# Power_Distribution_-_Spare_1-4.net
KiCad netlist of a schematic drawn in Altium Designer
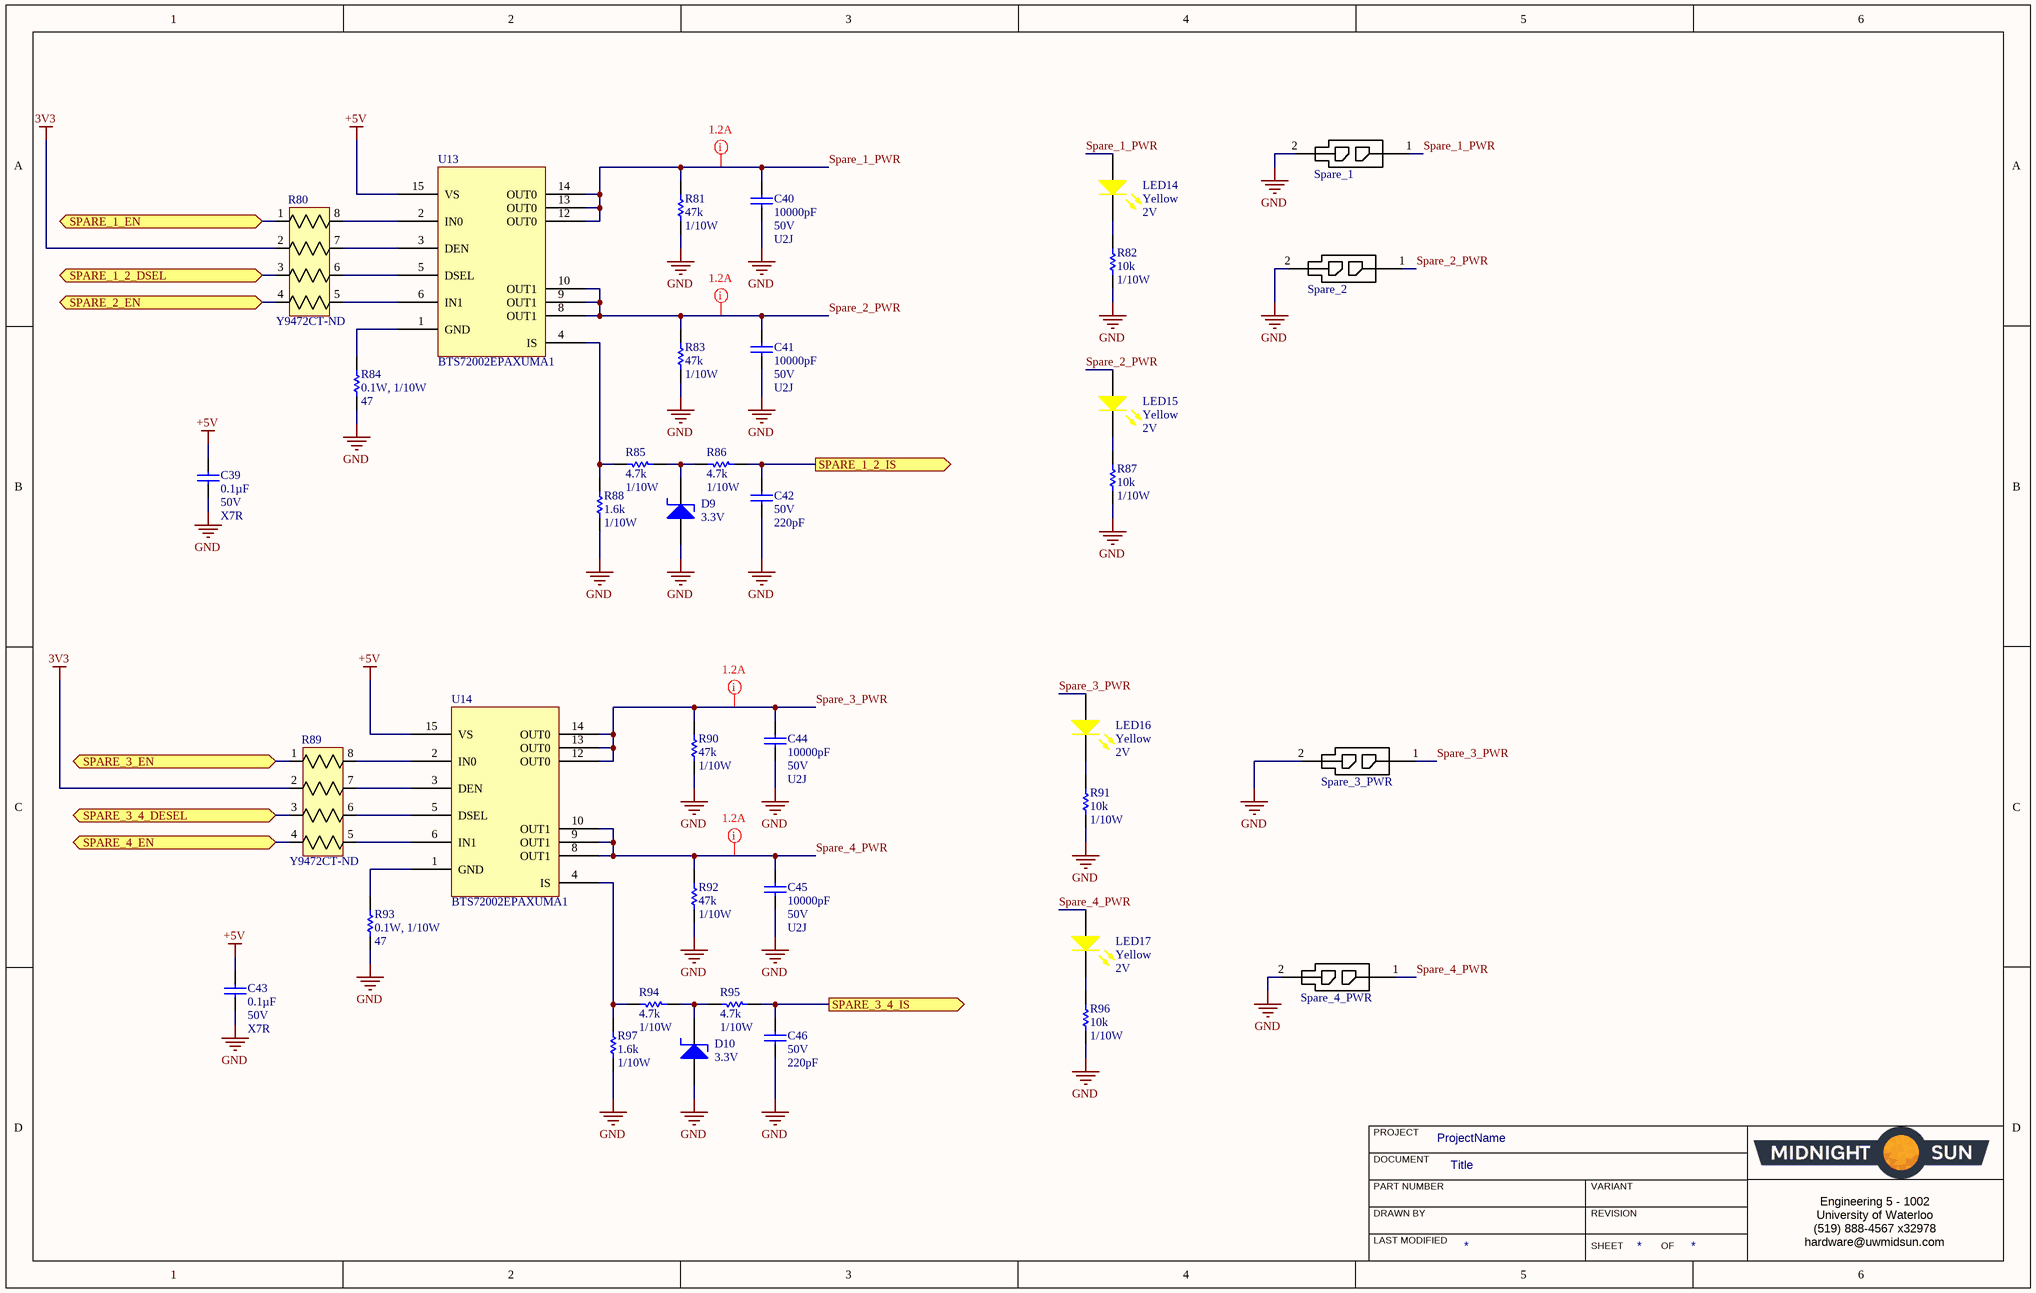
[diagram p0: Power Distribution - Spare 1-4.SchDoc]

(export (version "E")
  (design (tool "Eeschema 10.0.6"))
  (components
    (comp (ref "C39")
      (value "CAP CER 0.1UF 50V 10% X7R 0603")
      (footprint "CAP, 0603")
      (description "0.10µF ±10% 50V Ceramic Capacitor X7R 0603 (1608 Metric)")
      (fields
        (field (name "TOLERANCE") "±10%")
        (field (name "CAPACITANCE") "0.1µF")
        (field (name "VOLTAGE") "50V")
        (field (name "TEMPERATURE COEFFICIENT") "X7R")
      )
      (libsource (lib "Schematic Diagrams") (part "CAP CER 0.1UF 50V 10% X7R 0603"))
    )
    (comp (ref "C40")
      (value "CAP CER 10nF 50V 5% X7R 0603")
      (footprint "CAP, 0603")
      (description "10000pF ±5% 50V Ceramic Capacitor U2J 0603 (1608 Metric)")
      (fields
        (field (name "TOLERANCE") "±5%")
        (field (name "CAPACITANCE") "10000pF")
        (field (name "VOLTAGE") "50V")
        (field (name "TEMPERATURE COEFFICIENT") "U2J")
      )
      (libsource (lib "Schematic Diagrams") (part "CAP CER 10nF 50V 5% X7R 0603"))
    )
    (comp (ref "C41")
      (value "CAP CER 10nF 50V 5% X7R 0603")
      (footprint "CAP, 0603")
      (description "10000pF ±5% 50V Ceramic Capacitor U2J 0603 (1608 Metric)")
      (fields
        (field (name "TOLERANCE") "±5%")
        (field (name "CAPACITANCE") "10000pF")
        (field (name "VOLTAGE") "50V")
        (field (name "TEMPERATURE COEFFICIENT") "U2J")
      )
      (libsource (lib "Schematic Diagrams") (part "CAP CER 10nF 50V 5% X7R 0603"))
    )
    (comp (ref "C42")
      (value "CAP CER 220PF 50V C0G/NP0 0603")
      (footprint "CAP, 0603")
      (description "220pF ±5% 50V Ceramic Capacitor C0G, NP0 0603 (1608 Metric)")
      (fields
        (field (name "MANUFACTURER") "KEMET")
        (field (name "TOLERANCE") "5%")
        (field (name "VOLTAGE RATING") "50V")
        (field (name "CAPACITANCE") "220pF")
      )
      (libsource (lib "Schematic Diagrams") (part "CAP CER 220PF 50V C0G/NP0 0603"))
    )
    (comp (ref "C43")
      (value "CAP CER 0.1UF 50V 10% X7R 0603")
      (footprint "CAP, 0603")
      (description "0.10µF ±10% 50V Ceramic Capacitor X7R 0603 (1608 Metric)")
      (fields
        (field (name "TOLERANCE") "±10%")
        (field (name "CAPACITANCE") "0.1µF")
        (field (name "VOLTAGE") "50V")
        (field (name "TEMPERATURE COEFFICIENT") "X7R")
      )
      (libsource (lib "Schematic Diagrams") (part "CAP CER 0.1UF 50V 10% X7R 0603"))
    )
    (comp (ref "C44")
      (value "CAP CER 10nF 50V 5% X7R 0603")
      (footprint "CAP, 0603")
      (description "10000pF ±5% 50V Ceramic Capacitor U2J 0603 (1608 Metric)")
      (fields
        (field (name "TOLERANCE") "±5%")
        (field (name "CAPACITANCE") "10000pF")
        (field (name "VOLTAGE") "50V")
        (field (name "TEMPERATURE COEFFICIENT") "U2J")
      )
      (libsource (lib "Schematic Diagrams") (part "CAP CER 10nF 50V 5% X7R 0603"))
    )
    (comp (ref "C45")
      (value "CAP CER 10nF 50V 5% X7R 0603")
      (footprint "CAP, 0603")
      (description "10000pF ±5% 50V Ceramic Capacitor U2J 0603 (1608 Metric)")
      (fields
        (field (name "TOLERANCE") "±5%")
        (field (name "CAPACITANCE") "10000pF")
        (field (name "VOLTAGE") "50V")
        (field (name "TEMPERATURE COEFFICIENT") "U2J")
      )
      (libsource (lib "Schematic Diagrams") (part "CAP CER 10nF 50V 5% X7R 0603"))
    )
    (comp (ref "C46")
      (value "CAP CER 220PF 50V C0G/NP0 0603")
      (footprint "CAP, 0603")
      (description "220pF ±5% 50V Ceramic Capacitor C0G, NP0 0603 (1608 Metric)")
      (fields
        (field (name "MANUFACTURER") "KEMET")
        (field (name "TOLERANCE") "5%")
        (field (name "VOLTAGE RATING") "50V")
        (field (name "CAPACITANCE") "220pF")
      )
      (libsource (lib "Schematic Diagrams") (part "CAP CER 220PF 50V C0G/NP0 0603"))
    )
    (comp (ref "D9")
      (value "DIODE ZENER 3.3V 200MW SOD323")
      (footprint "sod-323")
      (description "Zener Diode 3.3V 200mW ±5% Surface Mount SOD-323")
      (fields (field (name "VOLTAGE") "3.3V"))
      (libsource (lib "Schematic Diagrams") (part "DIODE ZENER 3.3V 200MW SOD323"))
    )
    (comp (ref "D10")
      (value "DIODE ZENER 3.3V 200MW SOD323")
      (footprint "sod-323")
      (description "Zener Diode 3.3V 200mW ±5% Surface Mount SOD-323")
      (fields (field (name "VOLTAGE") "3.3V"))
      (libsource (lib "Schematic Diagrams") (part "DIODE ZENER 3.3V 200MW SOD323"))
    )
    (comp (ref "LED14")
      (value "LED YELLOW CLEAR 2.1V 0603")
      (footprint "LED_0603")
      (description "Yellow 590nm LED Indication - Discrete 2V 0603 (1608 Metric)")
      (fields
        (field (name "MANUFACTURER") "Wurth Electronics Inc.")
        (field (name "MANUFACTURER PART NUMBER") "150060YS75000")
        (field (name "COLOR") "Yellow")
        (field (name "VOLTAGE - FORWARD (VF) (TYP)") "2V")
      )
      (libsource (lib "Schematic Diagrams") (part "LED YELLOW CLEAR 2.1V 0603"))
    )
    (comp (ref "LED15")
      (value "LED YELLOW CLEAR 2.1V 0603")
      (footprint "LED_0603")
      (description "Yellow 590nm LED Indication - Discrete 2V 0603 (1608 Metric)")
      (fields
        (field (name "MANUFACTURER") "Wurth Electronics Inc.")
        (field (name "MANUFACTURER PART NUMBER") "150060YS75000")
        (field (name "COLOR") "Yellow")
        (field (name "VOLTAGE - FORWARD (VF) (TYP)") "2V")
      )
      (libsource (lib "Schematic Diagrams") (part "LED YELLOW CLEAR 2.1V 0603"))
    )
    (comp (ref "LED16")
      (value "LED YELLOW CLEAR 2.1V 0603")
      (footprint "LED_0603")
      (description "Yellow 590nm LED Indication - Discrete 2V 0603 (1608 Metric)")
      (fields
        (field (name "MANUFACTURER") "Wurth Electronics Inc.")
        (field (name "MANUFACTURER PART NUMBER") "150060YS75000")
        (field (name "COLOR") "Yellow")
        (field (name "VOLTAGE - FORWARD (VF) (TYP)") "2V")
      )
      (libsource (lib "Schematic Diagrams") (part "LED YELLOW CLEAR 2.1V 0603"))
    )
    (comp (ref "LED17")
      (value "LED YELLOW CLEAR 2.1V 0603")
      (footprint "LED_0603")
      (description "Yellow 590nm LED Indication - Discrete 2V 0603 (1608 Metric)")
      (fields
        (field (name "MANUFACTURER") "Wurth Electronics Inc.")
        (field (name "MANUFACTURER PART NUMBER") "150060YS75000")
        (field (name "COLOR") "Yellow")
        (field (name "VOLTAGE - FORWARD (VF) (TYP)") "2V")
      )
      (libsource (lib "Schematic Diagrams") (part "LED YELLOW CLEAR 2.1V 0603"))
    )
    (comp (ref "R80")
      (value "RES ARRAY 4 RES 4.7K OHM 1206")
      (footprint "RES ARRAY 4RES 1206")
      (fields (field (name "TOLERANCE") "±5%") (field (name "SUPPLIER PART NUMBER 1") "Y9472CT-ND"))
      (libsource (lib "Schematic Diagrams") (part "RES ARRAY 4 RES 4.7K OHM 1206"))
    )
    (comp (ref "R81")
      (value "RES 47K OHM 1% 1/10W 0603")
      (footprint "RES, 0603")
      (description "47 kOhms ±1% 0.1W, 1/10W Chip Resistor 0603 (1608 Metric) Automotive AEC-Q200 Thick Film")
      (fields
        (field (name "MANUFACTURER") "Panasonic")
        (field (name "MANUFACTURER PART NUMBER") "ERJ3EKF4702V")
        (field (name "RESISTANCE") "47k")
        (field (name "POWER RATING") "1/10W")
      )
      (libsource (lib "Schematic Diagrams") (part "RES 47K OHM 1% 1/10W 0603"))
    )
    (comp (ref "R82")
      (value "RES 10K OHM 1% 1/10W 0603")
      (footprint "RES, 0603")
      (description "RES SMD 10K OHM 1% 1/10W 0603")
      (fields
        (field (name "TOLERANCE") "±1%")
        (field (name "RESISTANCE") "10k")
        (field (name "POWER") "1/10W")
      )
      (libsource (lib "Schematic Diagrams") (part "RES 10K OHM 1% 1/10W 0603"))
    )
    (comp (ref "R83")
      (value "RES 47K OHM 1% 1/10W 0603")
      (footprint "RES, 0603")
      (description "47 kOhms ±1% 0.1W, 1/10W Chip Resistor 0603 (1608 Metric) Automotive AEC-Q200 Thick Film")
      (fields
        (field (name "MANUFACTURER") "Panasonic")
        (field (name "MANUFACTURER PART NUMBER") "ERJ3EKF4702V")
        (field (name "RESISTANCE") "47k")
        (field (name "POWER RATING") "1/10W")
      )
      (libsource (lib "Schematic Diagrams") (part "RES 47K OHM 1% 1/10W 0603"))
    )
    (comp (ref "R84")
      (value "RES SMD 47 OHM 1% 1/10W 0603")
      (footprint "RES, 0603")
      (fields
        (field (name "TOLERANCE") "±1%")
        (field (name "POWER (WATTS)") "0.1W, 1/10W")
        (field (name "VALUES") "47")
      )
      (libsource (lib "Schematic Diagrams") (part "RES SMD 47 OHM 1% 1/10W 0603"))
    )
    (comp (ref "R85")
      (value "RES 4.7K OHM 1% 1/10W 0603")
      (footprint "RES, 0603")
      (description "4.7k Ohm ±1% 0.1W, 1/10W Chip Resistor 0603 (1608 Metric) Moisture Resistant Thick Film")
      (fields
        (field (name "TOLERANCE") "±1%")
        (field (name "RESISTANCE (OHMS)") "4.7k")
        (field (name "POWER (WATTS)") "1/10W")
      )
      (libsource (lib "Schematic Diagrams") (part "RES 4.7K OHM 1% 1/10W 0603"))
    )
    (comp (ref "R86")
      (value "RES 4.7K OHM 1% 1/10W 0603")
      (footprint "RES, 0603")
      (description "4.7k Ohm ±1% 0.1W, 1/10W Chip Resistor 0603 (1608 Metric) Moisture Resistant Thick Film")
      (fields
        (field (name "TOLERANCE") "±1%")
        (field (name "RESISTANCE (OHMS)") "4.7k")
        (field (name "POWER (WATTS)") "1/10W")
      )
      (libsource (lib "Schematic Diagrams") (part "RES 4.7K OHM 1% 1/10W 0603"))
    )
    (comp (ref "R87")
      (value "RES 10K OHM 1% 1/10W 0603")
      (footprint "RES, 0603")
      (description "RES SMD 10K OHM 1% 1/10W 0603")
      (fields
        (field (name "TOLERANCE") "±1%")
        (field (name "RESISTANCE") "10k")
        (field (name "POWER") "1/10W")
      )
      (libsource (lib "Schematic Diagrams") (part "RES 10K OHM 1% 1/10W 0603"))
    )
    (comp (ref "R88")
      (value "RES 1.6K OHM 1% 1/10W 0603")
      (footprint "RES, 0603")
      (description "1.6 kOhms ±1% 0.1W, 1/10W Chip Resistor 0603 (1608 Metric) Moisture Resistant Thick Film")
      (fields
        (field (name "MANUFACTURER") "Yageo")
        (field (name "MANUFACTURER PART NUMBER") "RC0603FR-071K6L")
        (field (name "RESISTANCE") "1.6k")
        (field (name "POWER RATING") "1/10W")
      )
      (libsource (lib "Schematic Diagrams") (part "RES 1.6K OHM 1% 1/10W 0603"))
    )
    (comp (ref "R89")
      (value "RES ARRAY 4 RES 4.7K OHM 1206")
      (footprint "RES ARRAY 4RES 1206")
      (fields (field (name "TOLERANCE") "±5%") (field (name "SUPPLIER PART NUMBER 1") "Y9472CT-ND"))
      (libsource (lib "Schematic Diagrams") (part "RES ARRAY 4 RES 4.7K OHM 1206"))
    )
    (comp (ref "R90")
      (value "RES 47K OHM 1% 1/10W 0603")
      (footprint "RES, 0603")
      (description "47 kOhms ±1% 0.1W, 1/10W Chip Resistor 0603 (1608 Metric) Automotive AEC-Q200 Thick Film")
      (fields
        (field (name "MANUFACTURER") "Panasonic")
        (field (name "MANUFACTURER PART NUMBER") "ERJ3EKF4702V")
        (field (name "RESISTANCE") "47k")
        (field (name "POWER RATING") "1/10W")
      )
      (libsource (lib "Schematic Diagrams") (part "RES 47K OHM 1% 1/10W 0603"))
    )
    (comp (ref "R91")
      (value "RES 10K OHM 1% 1/10W 0603")
      (footprint "RES, 0603")
      (description "RES SMD 10K OHM 1% 1/10W 0603")
      (fields
        (field (name "TOLERANCE") "±1%")
        (field (name "RESISTANCE") "10k")
        (field (name "POWER") "1/10W")
      )
      (libsource (lib "Schematic Diagrams") (part "RES 10K OHM 1% 1/10W 0603"))
    )
    (comp (ref "R92")
      (value "RES 47K OHM 1% 1/10W 0603")
      (footprint "RES, 0603")
      (description "47 kOhms ±1% 0.1W, 1/10W Chip Resistor 0603 (1608 Metric) Automotive AEC-Q200 Thick Film")
      (fields
        (field (name "MANUFACTURER") "Panasonic")
        (field (name "MANUFACTURER PART NUMBER") "ERJ3EKF4702V")
        (field (name "RESISTANCE") "47k")
        (field (name "POWER RATING") "1/10W")
      )
      (libsource (lib "Schematic Diagrams") (part "RES 47K OHM 1% 1/10W 0603"))
    )
    (comp (ref "R93")
      (value "RES SMD 47 OHM 1% 1/10W 0603")
      (footprint "RES, 0603")
      (fields
        (field (name "TOLERANCE") "±1%")
        (field (name "POWER (WATTS)") "0.1W, 1/10W")
        (field (name "VALUES") "47")
      )
      (libsource (lib "Schematic Diagrams") (part "RES SMD 47 OHM 1% 1/10W 0603"))
    )
    (comp (ref "R94")
      (value "RES 4.7K OHM 1% 1/10W 0603")
      (footprint "RES, 0603")
      (description "4.7k Ohm ±1% 0.1W, 1/10W Chip Resistor 0603 (1608 Metric) Moisture Resistant Thick Film")
      (fields
        (field (name "TOLERANCE") "±1%")
        (field (name "RESISTANCE (OHMS)") "4.7k")
        (field (name "POWER (WATTS)") "1/10W")
      )
      (libsource (lib "Schematic Diagrams") (part "RES 4.7K OHM 1% 1/10W 0603"))
    )
    (comp (ref "R95")
      (value "RES 4.7K OHM 1% 1/10W 0603")
      (footprint "RES, 0603")
      (description "4.7k Ohm ±1% 0.1W, 1/10W Chip Resistor 0603 (1608 Metric) Moisture Resistant Thick Film")
      (fields
        (field (name "TOLERANCE") "±1%")
        (field (name "RESISTANCE (OHMS)") "4.7k")
        (field (name "POWER (WATTS)") "1/10W")
      )
      (libsource (lib "Schematic Diagrams") (part "RES 4.7K OHM 1% 1/10W 0603"))
    )
    (comp (ref "R96")
      (value "RES 10K OHM 1% 1/10W 0603")
      (footprint "RES, 0603")
      (description "RES SMD 10K OHM 1% 1/10W 0603")
      (fields
        (field (name "TOLERANCE") "±1%")
        (field (name "RESISTANCE") "10k")
        (field (name "POWER") "1/10W")
      )
      (libsource (lib "Schematic Diagrams") (part "RES 10K OHM 1% 1/10W 0603"))
    )
    (comp (ref "R97")
      (value "RES 1.6K OHM 1% 1/10W 0603")
      (footprint "RES, 0603")
      (description "1.6 kOhms ±1% 0.1W, 1/10W Chip Resistor 0603 (1608 Metric) Moisture Resistant Thick Film")
      (fields
        (field (name "MANUFACTURER") "Yageo")
        (field (name "MANUFACTURER PART NUMBER") "RC0603FR-071K6L")
        (field (name "RESISTANCE") "1.6k")
        (field (name "POWER RATING") "1/10W")
      )
      (libsource (lib "Schematic Diagrams") (part "RES 1.6K OHM 1% 1/10W 0603"))
    )
    (comp (ref "Spare_1")
      (value "CONN 2POS MICRO-FIT 3mm")
      (footprint "CONN, 2POS MICRO-FIT")
      (description "Connector Header Through Hole 2 position")
      (fields (field (name "MANUFACTURER") "Molex") (field (name "MANUFACTURER PART NUMBER") "43045-0227"))
      (libsource (lib "Schematic Diagrams") (part "CONN 2POS MICRO-FIT 3mm"))
    )
    (comp (ref "Spare_2")
      (value "CONN 2POS MICRO-FIT 3mm")
      (footprint "CONN, 2POS MICRO-FIT")
      (description "Connector Header Through Hole 2 position")
      (fields (field (name "MANUFACTURER") "Molex") (field (name "MANUFACTURER PART NUMBER") "43045-0227"))
      (libsource (lib "Schematic Diagrams") (part "CONN 2POS MICRO-FIT 3mm"))
    )
    (comp (ref "Spare_3_PWR")
      (value "CONN 2POS MICRO-FIT 3mm")
      (footprint "CONN, 2POS MICRO-FIT")
      (description "Connector Header Through Hole 2 position")
      (fields (field (name "MANUFACTURER") "Molex") (field (name "MANUFACTURER PART NUMBER") "43045-0227"))
      (libsource (lib "Schematic Diagrams") (part "CONN 2POS MICRO-FIT 3mm"))
    )
    (comp (ref "Spare_4_PWR")
      (value "CONN 2POS MICRO-FIT 3mm")
      (footprint "CONN, 2POS MICRO-FIT")
      (description "Connector Header Through Hole 2 position")
      (fields (field (name "MANUFACTURER") "Molex") (field (name "MANUFACTURER PART NUMBER") "43045-0227"))
      (libsource (lib "Schematic Diagrams") (part "CONN 2POS MICRO-FIT 3mm"))
    )
    (comp (ref "U13")
      (value "IC LOAD SWITCH BTS7200-2EPA PG-TSDSO-14_1")
      (footprint "IC LOAD SWITCH PG-TSDSO-14-22")
      (description "Power Switch/Driver 1:1 N-Channel 1.2A PG-TSDSO-14-22")
      (fields
        (field (name "MANUFACTURER") "Infineon")
        (field (name "MANUFACTURER PART NUMBER") "BTS72002EPAXUMA1")
      )
      (libsource (lib "Schematic Diagrams") (part "IC LOAD SWITCH BTS7200-2EPA PG-TSDSO-14_1"))
    )
    (comp (ref "U14")
      (value "IC LOAD SWITCH BTS7200-2EPA PG-TSDSO-14_1")
      (footprint "IC LOAD SWITCH PG-TSDSO-14-22")
      (description "Power Switch/Driver 1:1 N-Channel 1.2A PG-TSDSO-14-22")
      (fields
        (field (name "MANUFACTURER") "Infineon")
        (field (name "MANUFACTURER PART NUMBER") "BTS72002EPAXUMA1")
      )
      (libsource (lib "Schematic Diagrams") (part "IC LOAD SWITCH BTS7200-2EPA PG-TSDSO-14_1"))
    )
  )
  (nets
    (net (code "1") (name "+5V") (class "Default")
      (node (ref "C39") (pin "1") (pinfunction "1_1") (pintype "passive"))
      (node (ref "C43") (pin "1") (pinfunction "1_1") (pintype "passive"))
      (node (ref "U13") (pin "15") (pinfunction "VS_15") (pintype "passive"))
      (node (ref "U14") (pin "15") (pinfunction "VS_15") (pintype "passive"))
    )
    (net (code "2") (name "/SPARE_1_2_DSEL") (class "Default")
      (node (ref "R80") (pin "3") (pinfunction "3_3") (pintype "passive"))
    )
    (net (code "3") (name "/SPARE_1_2_IS") (class "Default")
      (node (ref "C42") (pin "1") (pinfunction "1_1") (pintype "passive"))
      (node (ref "R86") (pin "1") (pinfunction "1_1") (pintype "passive"))
    )
    (net (code "4") (name "/SPARE_1_EN") (class "Default")
      (node (ref "R80") (pin "1") (pinfunction "1_1") (pintype "passive"))
    )
    (net (code "5") (name "/SPARE_2_EN") (class "Default")
      (node (ref "R80") (pin "4") (pinfunction "4_4") (pintype "passive"))
    )
    (net (code "6") (name "/SPARE_3_4_DESEL") (class "Default")
      (node (ref "R89") (pin "3") (pinfunction "3_3") (pintype "passive"))
    )
    (net (code "7") (name "/SPARE_3_4_IS") (class "Default")
      (node (ref "C46") (pin "1") (pinfunction "1_1") (pintype "passive"))
      (node (ref "R95") (pin "1") (pinfunction "1_1") (pintype "passive"))
    )
    (net (code "8") (name "/SPARE_3_EN") (class "Default")
      (node (ref "R89") (pin "1") (pinfunction "1_1") (pintype "passive"))
    )
    (net (code "9") (name "/SPARE_4_EN") (class "Default")
      (node (ref "R89") (pin "4") (pinfunction "4_4") (pintype "passive"))
    )
    (net (code "10") (name "/Spare_1_PWR") (class "Default")
      (node (ref "C40") (pin "1") (pinfunction "1_1") (pintype "passive"))
      (node (ref "LED14") (pin "1") (pinfunction "A_1") (pintype "passive"))
      (node (ref "R81") (pin "1") (pinfunction "1_1") (pintype "passive"))
      (node (ref "Spare_1") (pin "1") (pinfunction "1_1") (pintype "passive"))
      (node (ref "U13") (pin "12") (pinfunction "OUT0_12") (pintype "passive"))
      (node (ref "U13") (pin "13") (pinfunction "OUT0_13") (pintype "passive"))
      (node (ref "U13") (pin "14") (pinfunction "OUT0_14") (pintype "passive"))
    )
    (net (code "11") (name "/Spare_2_PWR") (class "Default")
      (node (ref "C41") (pin "1") (pinfunction "1_1") (pintype "passive"))
      (node (ref "LED15") (pin "1") (pinfunction "A_1") (pintype "passive"))
      (node (ref "R83") (pin "1") (pinfunction "1_1") (pintype "passive"))
      (node (ref "Spare_2") (pin "1") (pinfunction "1_1") (pintype "passive"))
      (node (ref "U13") (pin "10") (pinfunction "OUT1_10") (pintype "passive"))
      (node (ref "U13") (pin "8") (pinfunction "OUT1_8") (pintype "passive"))
      (node (ref "U13") (pin "9") (pinfunction "OUT1_9") (pintype "passive"))
    )
    (net (code "12") (name "/Spare_3_PWR") (class "Default")
      (node (ref "C44") (pin "1") (pinfunction "1_1") (pintype "passive"))
      (node (ref "LED16") (pin "1") (pinfunction "A_1") (pintype "passive"))
      (node (ref "R90") (pin "1") (pinfunction "1_1") (pintype "passive"))
      (node (ref "Spare_3_PWR") (pin "1") (pinfunction "1_1") (pintype "passive"))
      (node (ref "U14") (pin "12") (pinfunction "OUT0_12") (pintype "passive"))
      (node (ref "U14") (pin "13") (pinfunction "OUT0_13") (pintype "passive"))
      (node (ref "U14") (pin "14") (pinfunction "OUT0_14") (pintype "passive"))
    )
    (net (code "13") (name "/Spare_4_PWR") (class "Default")
      (node (ref "C45") (pin "1") (pinfunction "1_1") (pintype "passive"))
      (node (ref "LED17") (pin "1") (pinfunction "A_1") (pintype "passive"))
      (node (ref "R92") (pin "1") (pinfunction "1_1") (pintype "passive"))
      (node (ref "Spare_4_PWR") (pin "1") (pinfunction "1_1") (pintype "passive"))
      (node (ref "U14") (pin "10") (pinfunction "OUT1_10") (pintype "passive"))
      (node (ref "U14") (pin "8") (pinfunction "OUT1_8") (pintype "passive"))
      (node (ref "U14") (pin "9") (pinfunction "OUT1_9") (pintype "passive"))
    )
    (net (code "14") (name "3V3") (class "Default")
      (node (ref "R80") (pin "2") (pinfunction "2_2") (pintype "passive"))
      (node (ref "R89") (pin "2") (pinfunction "2_2") (pintype "passive"))
    )
    (net (code "15") (name "GND") (class "Default")
      (node (ref "C39") (pin "2") (pinfunction "2_2") (pintype "passive"))
      (node (ref "C40") (pin "2") (pinfunction "2_2") (pintype "passive"))
      (node (ref "C41") (pin "2") (pinfunction "2_2") (pintype "passive"))
      (node (ref "C42") (pin "2") (pinfunction "2_2") (pintype "passive"))
      (node (ref "C43") (pin "2") (pinfunction "2_2") (pintype "passive"))
      (node (ref "C44") (pin "2") (pinfunction "2_2") (pintype "passive"))
      (node (ref "C45") (pin "2") (pinfunction "2_2") (pintype "passive"))
      (node (ref "C46") (pin "2") (pinfunction "2_2") (pintype "passive"))
      (node (ref "D10") (pin "1") (pinfunction "A_1") (pintype "passive"))
      (node (ref "D9") (pin "1") (pinfunction "A_1") (pintype "passive"))
      (node (ref "R81") (pin "2") (pinfunction "2_2") (pintype "passive"))
      (node (ref "R82") (pin "2") (pinfunction "2_2") (pintype "passive"))
      (node (ref "R83") (pin "2") (pinfunction "2_2") (pintype "passive"))
      (node (ref "R84") (pin "2") (pinfunction "2_2") (pintype "passive"))
      (node (ref "R87") (pin "2") (pinfunction "2_2") (pintype "passive"))
      (node (ref "R88") (pin "2") (pinfunction "2_2") (pintype "passive"))
      (node (ref "R90") (pin "2") (pinfunction "2_2") (pintype "passive"))
      (node (ref "R91") (pin "2") (pinfunction "2_2") (pintype "passive"))
      (node (ref "R92") (pin "2") (pinfunction "2_2") (pintype "passive"))
      (node (ref "R93") (pin "2") (pinfunction "2_2") (pintype "passive"))
      (node (ref "R96") (pin "2") (pinfunction "2_2") (pintype "passive"))
      (node (ref "R97") (pin "2") (pinfunction "2_2") (pintype "passive"))
      (node (ref "Spare_1") (pin "2") (pinfunction "2_2") (pintype "passive"))
      (node (ref "Spare_2") (pin "2") (pinfunction "2_2") (pintype "passive"))
      (node (ref "Spare_3_PWR") (pin "2") (pinfunction "2_2") (pintype "passive"))
      (node (ref "Spare_4_PWR") (pin "2") (pinfunction "2_2") (pintype "passive"))
    )
    (net (code "16") (name "Net-(D9-K)") (class "Default")
      (node (ref "D9") (pin "2") (pinfunction "K_2") (pintype "passive"))
      (node (ref "R85") (pin "1") (pinfunction "1_1") (pintype "passive"))
      (node (ref "R86") (pin "2") (pinfunction "2_2") (pintype "passive"))
    )
    (net (code "17") (name "Net-(D10-K)") (class "Default")
      (node (ref "D10") (pin "2") (pinfunction "K_2") (pintype "passive"))
      (node (ref "R94") (pin "1") (pinfunction "1_1") (pintype "passive"))
      (node (ref "R95") (pin "2") (pinfunction "2_2") (pintype "passive"))
    )
    (net (code "18") (name "Net-(LED14-K)") (class "Default")
      (node (ref "LED14") (pin "2") (pinfunction "K_2") (pintype "passive"))
      (node (ref "R82") (pin "1") (pinfunction "1_1") (pintype "passive"))
    )
    (net (code "19") (name "Net-(LED15-K)") (class "Default")
      (node (ref "LED15") (pin "2") (pinfunction "K_2") (pintype "passive"))
      (node (ref "R87") (pin "1") (pinfunction "1_1") (pintype "passive"))
    )
    (net (code "20") (name "Net-(LED16-K)") (class "Default")
      (node (ref "LED16") (pin "2") (pinfunction "K_2") (pintype "passive"))
      (node (ref "R91") (pin "1") (pinfunction "1_1") (pintype "passive"))
    )
    (net (code "21") (name "Net-(LED17-K)") (class "Default")
      (node (ref "LED17") (pin "2") (pinfunction "K_2") (pintype "passive"))
      (node (ref "R96") (pin "1") (pinfunction "1_1") (pintype "passive"))
    )
    (net (code "22") (name "Net-(U13-DEN)") (class "Default")
      (node (ref "R80") (pin "7") (pinfunction "7_7") (pintype "passive"))
      (node (ref "U13") (pin "3") (pinfunction "DEN_3") (pintype "passive"))
    )
    (net (code "23") (name "Net-(U13-DSEL)") (class "Default")
      (node (ref "R80") (pin "6") (pinfunction "6_6") (pintype "passive"))
      (node (ref "U13") (pin "5") (pinfunction "DSEL_5") (pintype "passive"))
    )
    (net (code "24") (name "Net-(U13-GND)") (class "Default")
      (node (ref "R84") (pin "1") (pinfunction "1_1") (pintype "passive"))
      (node (ref "U13") (pin "1") (pinfunction "GND_1") (pintype "passive"))
    )
    (net (code "25") (name "Net-(U13-IN0)") (class "Default")
      (node (ref "R80") (pin "8") (pinfunction "8_8") (pintype "passive"))
      (node (ref "U13") (pin "2") (pinfunction "IN0_2") (pintype "passive"))
    )
    (net (code "26") (name "Net-(U13-IN1)") (class "Default")
      (node (ref "R80") (pin "5") (pinfunction "5_5") (pintype "passive"))
      (node (ref "U13") (pin "6") (pinfunction "IN1_6") (pintype "passive"))
    )
    (net (code "27") (name "Net-(U13-IS)") (class "Default")
      (node (ref "R85") (pin "2") (pinfunction "2_2") (pintype "passive"))
      (node (ref "R88") (pin "1") (pinfunction "1_1") (pintype "passive"))
      (node (ref "U13") (pin "4") (pinfunction "IS_4") (pintype "passive"))
    )
    (net (code "28") (name "Net-(U14-DEN)") (class "Default")
      (node (ref "R89") (pin "7") (pinfunction "7_7") (pintype "passive"))
      (node (ref "U14") (pin "3") (pinfunction "DEN_3") (pintype "passive"))
    )
    (net (code "29") (name "Net-(U14-DSEL)") (class "Default")
      (node (ref "R89") (pin "6") (pinfunction "6_6") (pintype "passive"))
      (node (ref "U14") (pin "5") (pinfunction "DSEL_5") (pintype "passive"))
    )
    (net (code "30") (name "Net-(U14-GND)") (class "Default")
      (node (ref "R93") (pin "1") (pinfunction "1_1") (pintype "passive"))
      (node (ref "U14") (pin "1") (pinfunction "GND_1") (pintype "passive"))
    )
    (net (code "31") (name "Net-(U14-IN0)") (class "Default")
      (node (ref "R89") (pin "8") (pinfunction "8_8") (pintype "passive"))
      (node (ref "U14") (pin "2") (pinfunction "IN0_2") (pintype "passive"))
    )
    (net (code "32") (name "Net-(U14-IN1)") (class "Default")
      (node (ref "R89") (pin "5") (pinfunction "5_5") (pintype "passive"))
      (node (ref "U14") (pin "6") (pinfunction "IN1_6") (pintype "passive"))
    )
    (net (code "33") (name "Net-(U14-IS)") (class "Default")
      (node (ref "R94") (pin "2") (pinfunction "2_2") (pintype "passive"))
      (node (ref "R97") (pin "1") (pinfunction "1_1") (pintype "passive"))
      (node (ref "U14") (pin "4") (pinfunction "IS_4") (pintype "passive"))
    )
  )
)
